# Sheet1.net
KiCad netlist of a schematic drawn in Altium Designer
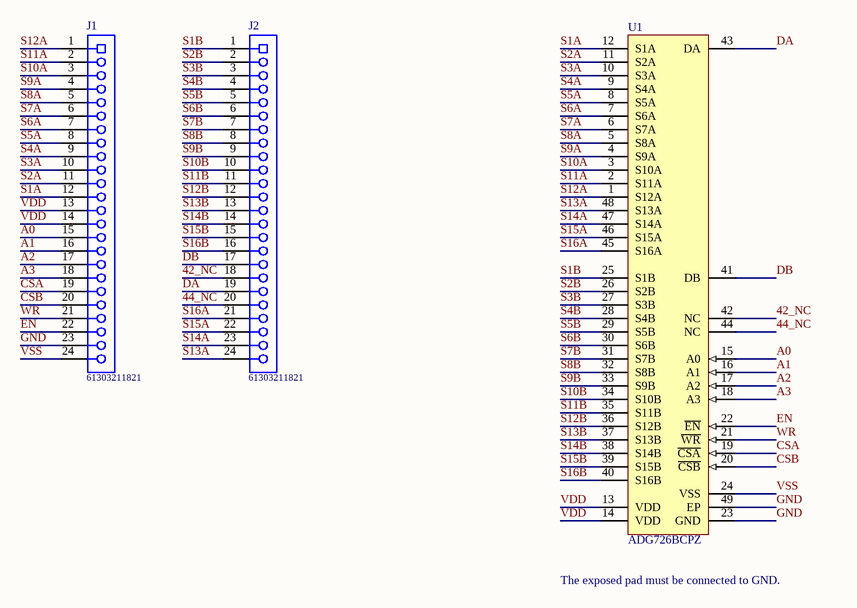
[diagram p0: Sheet1.SchDoc]

(export (version "E")
  (design (tool "Eeschema 10.0.6"))
  (components
    (comp (ref "J1")
      (value "61303211821")
      (footprint "61303211821")
      (description "THT Vertical Socket Header WR-PHD, Pitch 2.54 mm, Single Row, 32 pins")
      (fields (field (name "MANUFACTURER") "Wurth Elektronik") (field (name "PUBLISHER") "WurthElektronik"))
      (libsource (lib "Schlib1") (part "Header 1x24"))
    )
    (comp (ref "J2")
      (value "61303211821")
      (footprint "61303211821")
      (description "THT Vertical Socket Header WR-PHD, Pitch 2.54 mm, Single Row, 32 pins")
      (fields (field (name "MANUFACTURER") "Wurth Elektronik") (field (name "PUBLISHER") "WurthElektronik"))
      (libsource (lib "Schlib1") (part "Header 1x24"))
    )
    (comp (ref "U1")
      (value "ADG726BCPZ")
      (footprint "ADI-CP-48-1_M")
      (fields (field (name "MANUFACTURER") "Analog Devices"))
      (libsource (lib "Schlib1") (part "CMP-0798-00018-1"))
    )
  )
  (nets
    (net (code "1") (name "/42_NC") (class "Default")
      (node (ref "J2") (pin "18") (pinfunction "18_18") (pintype "passive"))
      (node (ref "U1") (pin "42") (pinfunction "NC_42") (pintype "passive"))
    )
    (net (code "2") (name "/44_NC") (class "Default")
      (node (ref "J2") (pin "20") (pinfunction "20_20") (pintype "passive"))
      (node (ref "U1") (pin "44") (pinfunction "NC_44") (pintype "passive"))
    )
    (net (code "3") (name "/A0") (class "Default")
      (node (ref "J1") (pin "15") (pinfunction "15_15") (pintype "passive"))
      (node (ref "U1") (pin "15") (pinfunction "A0_15") (pintype "input"))
    )
    (net (code "4") (name "/A1") (class "Default")
      (node (ref "J1") (pin "16") (pinfunction "16_16") (pintype "passive"))
      (node (ref "U1") (pin "16") (pinfunction "A1_16") (pintype "input"))
    )
    (net (code "5") (name "/A2") (class "Default")
      (node (ref "J1") (pin "17") (pinfunction "17_17") (pintype "passive"))
      (node (ref "U1") (pin "17") (pinfunction "A2_17") (pintype "input"))
    )
    (net (code "6") (name "/A3") (class "Default")
      (node (ref "J1") (pin "18") (pinfunction "18_18") (pintype "passive"))
      (node (ref "U1") (pin "18") (pinfunction "A3_18") (pintype "input"))
    )
    (net (code "7") (name "/CSA") (class "Default")
      (node (ref "J1") (pin "19") (pinfunction "19_19") (pintype "passive"))
      (node (ref "U1") (pin "19") (pinfunction "~{CSA}_19") (pintype "input"))
    )
    (net (code "8") (name "/CSB") (class "Default")
      (node (ref "J1") (pin "20") (pinfunction "20_20") (pintype "passive"))
      (node (ref "U1") (pin "20") (pinfunction "~{CSB}_20") (pintype "input"))
    )
    (net (code "9") (name "/DA") (class "Default")
      (node (ref "J2") (pin "19") (pinfunction "19_19") (pintype "passive"))
      (node (ref "U1") (pin "43") (pinfunction "DA_43") (pintype "passive"))
    )
    (net (code "10") (name "/DB") (class "Default")
      (node (ref "J2") (pin "17") (pinfunction "17_17") (pintype "passive"))
      (node (ref "U1") (pin "41") (pinfunction "DB_41") (pintype "passive"))
    )
    (net (code "11") (name "/EN") (class "Default")
      (node (ref "J1") (pin "22") (pinfunction "22_22") (pintype "passive"))
      (node (ref "U1") (pin "22") (pinfunction "~{EN}_22") (pintype "input"))
    )
    (net (code "12") (name "/GND") (class "Default")
      (node (ref "J1") (pin "23") (pinfunction "23_23") (pintype "passive"))
      (node (ref "U1") (pin "23") (pinfunction "GND_23") (pintype "power_in"))
      (node (ref "U1") (pin "49") (pinfunction "EP_49") (pintype "passive"))
    )
    (net (code "13") (name "/S1A") (class "Default")
      (node (ref "J1") (pin "12") (pinfunction "12_12") (pintype "passive"))
      (node (ref "U1") (pin "12") (pinfunction "S1A_12") (pintype "passive"))
    )
    (net (code "14") (name "/S1B") (class "Default")
      (node (ref "J2") (pin "1") (pinfunction "1_1") (pintype "passive"))
      (node (ref "U1") (pin "25") (pinfunction "S1B_25") (pintype "passive"))
    )
    (net (code "15") (name "/S2A") (class "Default")
      (node (ref "J1") (pin "11") (pinfunction "11_11") (pintype "passive"))
      (node (ref "U1") (pin "11") (pinfunction "S2A_11") (pintype "passive"))
    )
    (net (code "16") (name "/S2B") (class "Default")
      (node (ref "J2") (pin "2") (pinfunction "2_2") (pintype "passive"))
      (node (ref "U1") (pin "26") (pinfunction "S2B_26") (pintype "passive"))
    )
    (net (code "17") (name "/S3A") (class "Default")
      (node (ref "J1") (pin "10") (pinfunction "10_10") (pintype "passive"))
      (node (ref "U1") (pin "10") (pinfunction "S3A_10") (pintype "passive"))
    )
    (net (code "18") (name "/S3B") (class "Default")
      (node (ref "J2") (pin "3") (pinfunction "3_3") (pintype "passive"))
      (node (ref "U1") (pin "27") (pinfunction "S3B_27") (pintype "passive"))
    )
    (net (code "19") (name "/S4A") (class "Default")
      (node (ref "J1") (pin "9") (pinfunction "9_9") (pintype "passive"))
      (node (ref "U1") (pin "9") (pinfunction "S4A_9") (pintype "passive"))
    )
    (net (code "20") (name "/S4B") (class "Default")
      (node (ref "J2") (pin "4") (pinfunction "4_4") (pintype "passive"))
      (node (ref "U1") (pin "28") (pinfunction "S4B_28") (pintype "passive"))
    )
    (net (code "21") (name "/S5A") (class "Default")
      (node (ref "J1") (pin "8") (pinfunction "8_8") (pintype "passive"))
      (node (ref "U1") (pin "8") (pinfunction "S5A_8") (pintype "passive"))
    )
    (net (code "22") (name "/S5B") (class "Default")
      (node (ref "J2") (pin "5") (pinfunction "5_5") (pintype "passive"))
      (node (ref "U1") (pin "29") (pinfunction "S5B_29") (pintype "passive"))
    )
    (net (code "23") (name "/S6A") (class "Default")
      (node (ref "J1") (pin "7") (pinfunction "7_7") (pintype "passive"))
      (node (ref "U1") (pin "7") (pinfunction "S6A_7") (pintype "passive"))
    )
    (net (code "24") (name "/S6B") (class "Default")
      (node (ref "J2") (pin "6") (pinfunction "6_6") (pintype "passive"))
      (node (ref "U1") (pin "30") (pinfunction "S6B_30") (pintype "passive"))
    )
    (net (code "25") (name "/S7A") (class "Default")
      (node (ref "J1") (pin "6") (pinfunction "6_6") (pintype "passive"))
      (node (ref "U1") (pin "6") (pinfunction "S7A_6") (pintype "passive"))
    )
    (net (code "26") (name "/S7B") (class "Default")
      (node (ref "J2") (pin "7") (pinfunction "7_7") (pintype "passive"))
      (node (ref "U1") (pin "31") (pinfunction "S7B_31") (pintype "passive"))
    )
    (net (code "27") (name "/S8A") (class "Default")
      (node (ref "J1") (pin "5") (pinfunction "5_5") (pintype "passive"))
      (node (ref "U1") (pin "5") (pinfunction "S8A_5") (pintype "passive"))
    )
    (net (code "28") (name "/S8B") (class "Default")
      (node (ref "J2") (pin "8") (pinfunction "8_8") (pintype "passive"))
      (node (ref "U1") (pin "32") (pinfunction "S8B_32") (pintype "passive"))
    )
    (net (code "29") (name "/S9A") (class "Default")
      (node (ref "J1") (pin "4") (pinfunction "4_4") (pintype "passive"))
      (node (ref "U1") (pin "4") (pinfunction "S9A_4") (pintype "passive"))
    )
    (net (code "30") (name "/S9B") (class "Default")
      (node (ref "J2") (pin "9") (pinfunction "9_9") (pintype "passive"))
      (node (ref "U1") (pin "33") (pinfunction "S9B_33") (pintype "passive"))
    )
    (net (code "31") (name "/S10A") (class "Default")
      (node (ref "J1") (pin "3") (pinfunction "3_3") (pintype "passive"))
      (node (ref "U1") (pin "3") (pinfunction "S10A_3") (pintype "passive"))
    )
    (net (code "32") (name "/S10B") (class "Default")
      (node (ref "J2") (pin "10") (pinfunction "10_10") (pintype "passive"))
      (node (ref "U1") (pin "34") (pinfunction "S10B_34") (pintype "passive"))
    )
    (net (code "33") (name "/S11A") (class "Default")
      (node (ref "J1") (pin "2") (pinfunction "2_2") (pintype "passive"))
      (node (ref "U1") (pin "2") (pinfunction "S11A_2") (pintype "passive"))
    )
    (net (code "34") (name "/S11B") (class "Default")
      (node (ref "J2") (pin "11") (pinfunction "11_11") (pintype "passive"))
      (node (ref "U1") (pin "35") (pinfunction "S11B_35") (pintype "passive"))
    )
    (net (code "35") (name "/S12A") (class "Default")
      (node (ref "J1") (pin "1") (pinfunction "1_1") (pintype "passive"))
      (node (ref "U1") (pin "1") (pinfunction "S12A_1") (pintype "passive"))
    )
    (net (code "36") (name "/S12B") (class "Default")
      (node (ref "J2") (pin "12") (pinfunction "12_12") (pintype "passive"))
      (node (ref "U1") (pin "36") (pinfunction "S12B_36") (pintype "passive"))
    )
    (net (code "37") (name "/S13A") (class "Default")
      (node (ref "J2") (pin "24") (pinfunction "24_24") (pintype "passive"))
      (node (ref "U1") (pin "48") (pinfunction "S13A_48") (pintype "passive"))
    )
    (net (code "38") (name "/S13B") (class "Default")
      (node (ref "J2") (pin "13") (pinfunction "13_13") (pintype "passive"))
      (node (ref "U1") (pin "37") (pinfunction "S13B_37") (pintype "passive"))
    )
    (net (code "39") (name "/S14A") (class "Default")
      (node (ref "J2") (pin "23") (pinfunction "23_23") (pintype "passive"))
      (node (ref "U1") (pin "47") (pinfunction "S14A_47") (pintype "passive"))
    )
    (net (code "40") (name "/S14B") (class "Default")
      (node (ref "J2") (pin "14") (pinfunction "14_14") (pintype "passive"))
      (node (ref "U1") (pin "38") (pinfunction "S14B_38") (pintype "passive"))
    )
    (net (code "41") (name "/S15A") (class "Default")
      (node (ref "J2") (pin "22") (pinfunction "22_22") (pintype "passive"))
      (node (ref "U1") (pin "46") (pinfunction "S15A_46") (pintype "passive"))
    )
    (net (code "42") (name "/S15B") (class "Default")
      (node (ref "J2") (pin "15") (pinfunction "15_15") (pintype "passive"))
      (node (ref "U1") (pin "39") (pinfunction "S15B_39") (pintype "passive"))
    )
    (net (code "43") (name "/S16A") (class "Default")
      (node (ref "J2") (pin "21") (pinfunction "21_21") (pintype "passive"))
      (node (ref "U1") (pin "45") (pinfunction "S16A_45") (pintype "passive"))
    )
    (net (code "44") (name "/S16B") (class "Default")
      (node (ref "J2") (pin "16") (pinfunction "16_16") (pintype "passive"))
      (node (ref "U1") (pin "40") (pinfunction "S16B_40") (pintype "passive"))
    )
    (net (code "45") (name "/VDD") (class "Default")
      (node (ref "J1") (pin "13") (pinfunction "13_13") (pintype "passive"))
      (node (ref "J1") (pin "14") (pinfunction "14_14") (pintype "passive"))
      (node (ref "U1") (pin "13") (pinfunction "VDD_13") (pintype "power_in"))
      (node (ref "U1") (pin "14") (pinfunction "VDD_14") (pintype "power_in"))
    )
    (net (code "46") (name "/VSS") (class "Default")
      (node (ref "J1") (pin "24") (pinfunction "24_24") (pintype "passive"))
      (node (ref "U1") (pin "24") (pinfunction "VSS_24") (pintype "power_in"))
    )
    (net (code "47") (name "/WR") (class "Default")
      (node (ref "J1") (pin "21") (pinfunction "21_21") (pintype "passive"))
      (node (ref "U1") (pin "21") (pinfunction "~{WR}_21") (pintype "input"))
    )
  )
)
